# LPCB226_-_TOP_OVERVIEW.net
KiCad netlist of a schematic drawn in Altium Designer
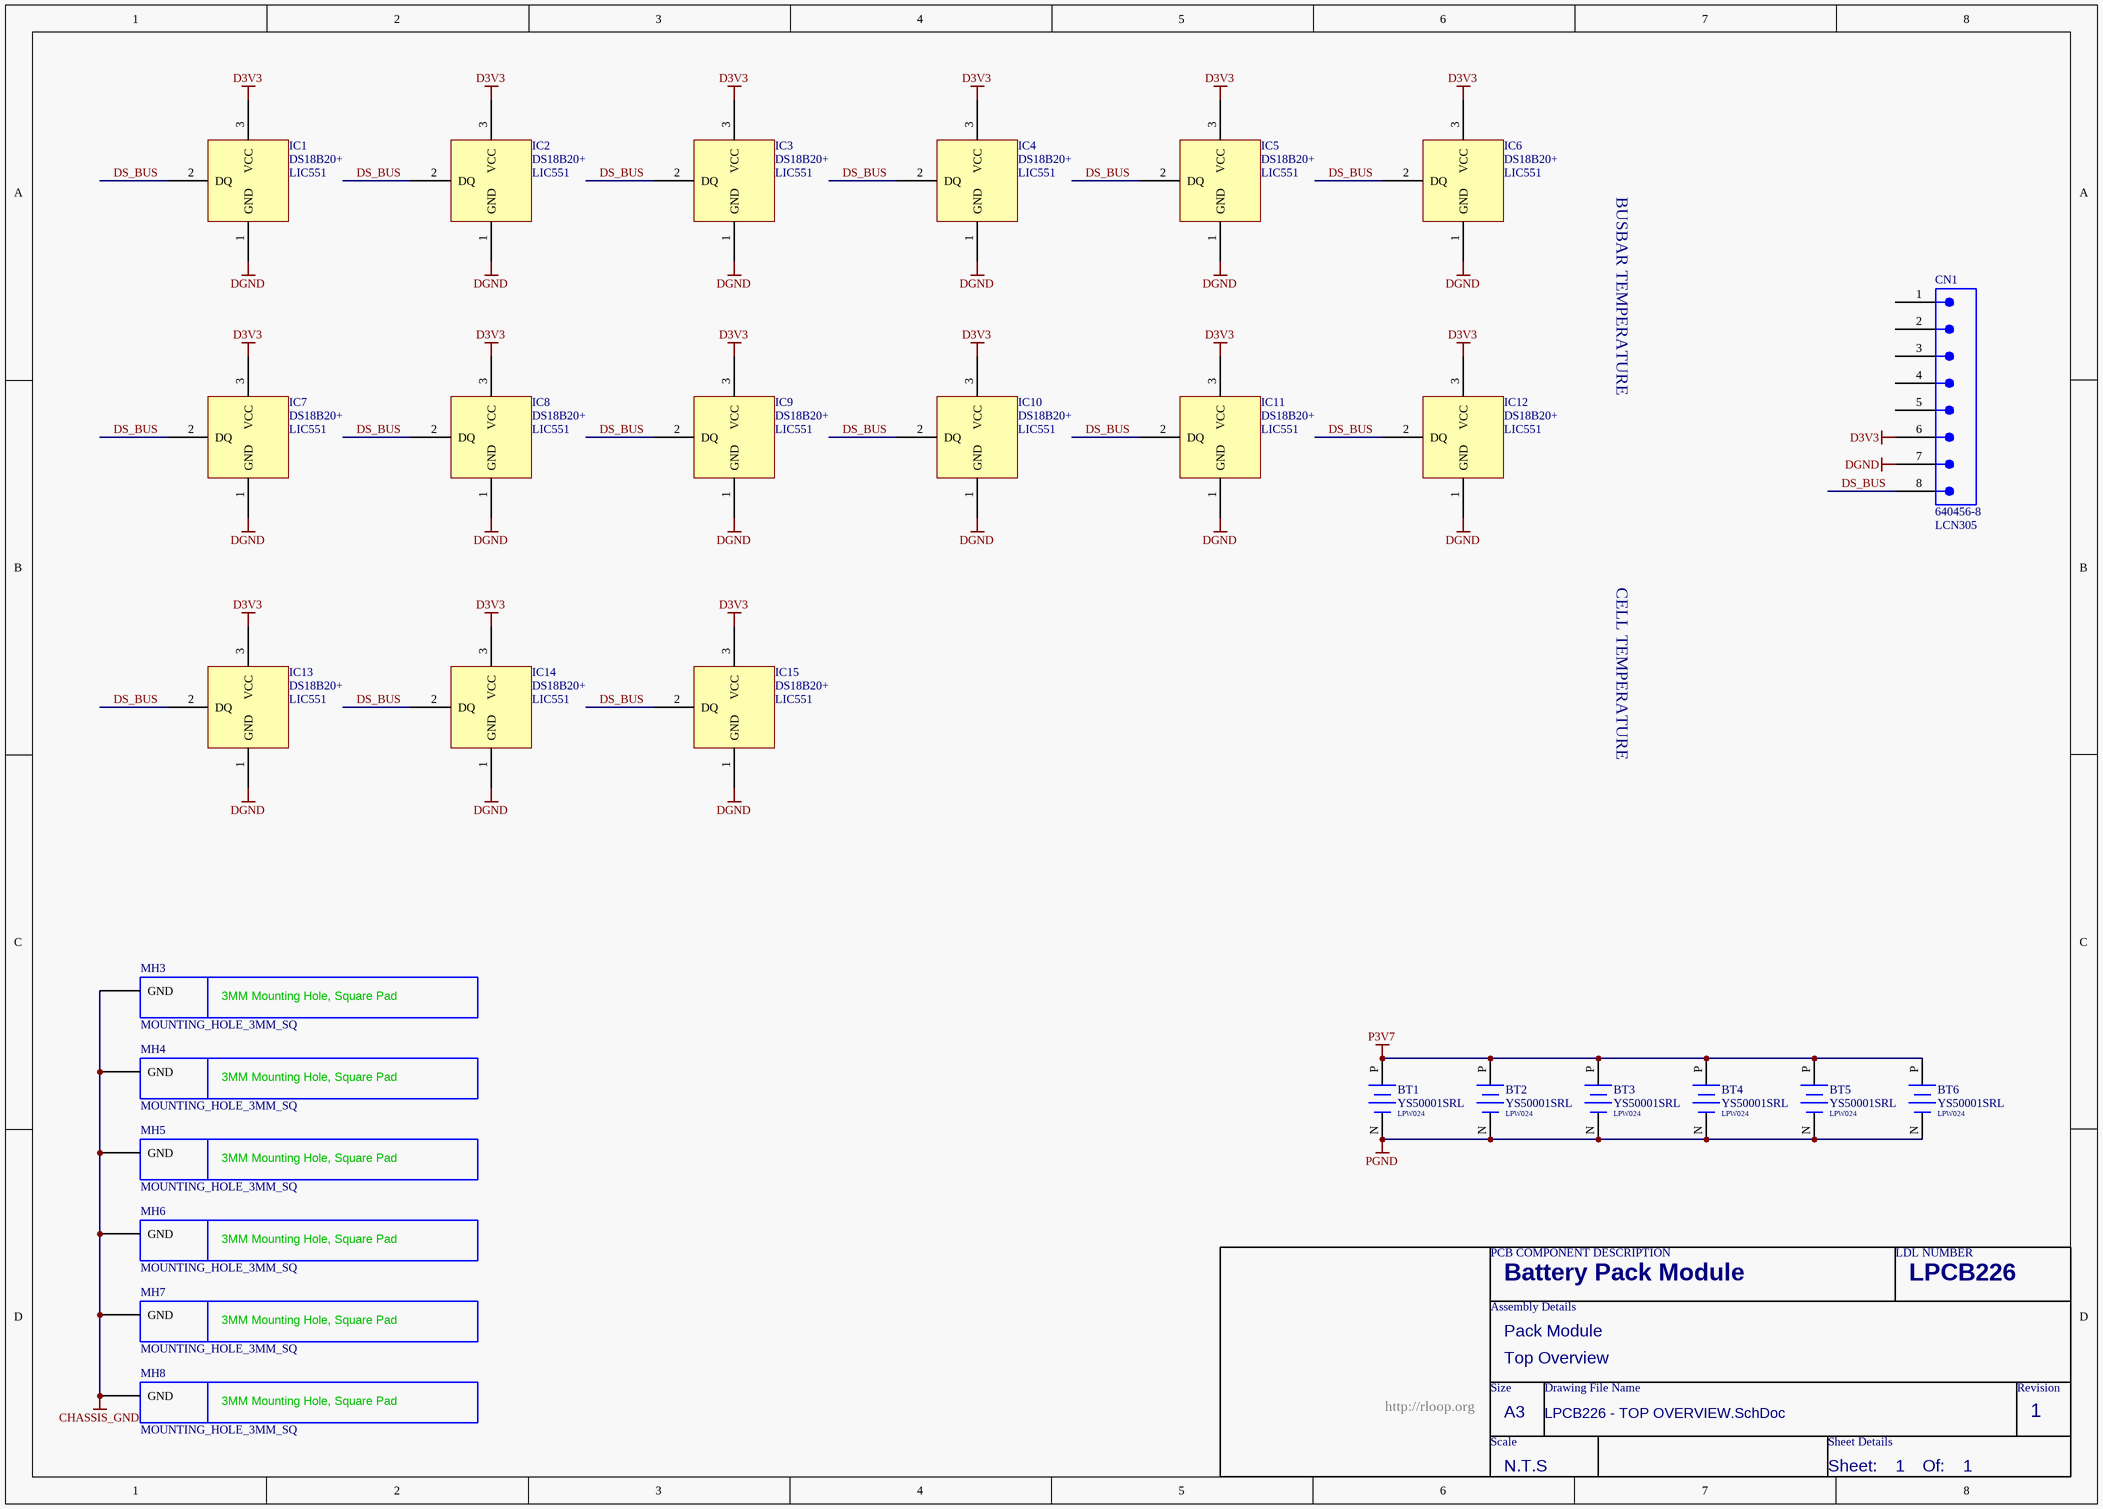
[diagram p0: LPCB226 - TOP OVERVIEW.SchDoc]

(export (version "E")
  (design (tool "Eeschema 10.0.6"))
  (components
    (comp (ref "BT1")
      (value "YS50001SRL")
      (footprint "YS50001SRL")
      (description "Battery, LiPo")
      (fields (field (name "LDL_NUMBER") "LPW024"))
      (libsource (lib "LDL_Power") (part "YS50001SRL"))
    )
    (comp (ref "BT2")
      (value "YS50001SRL")
      (footprint "YS50001SRL")
      (description "Battery, LiPo")
      (fields (field (name "LDL_NUMBER") "LPW024"))
      (libsource (lib "LDL_Power") (part "YS50001SRL"))
    )
    (comp (ref "BT3")
      (value "YS50001SRL")
      (footprint "YS50001SRL")
      (description "Battery, LiPo")
      (fields (field (name "LDL_NUMBER") "LPW024"))
      (libsource (lib "LDL_Power") (part "YS50001SRL"))
    )
    (comp (ref "BT4")
      (value "YS50001SRL")
      (footprint "YS50001SRL")
      (description "Battery, LiPo")
      (fields (field (name "LDL_NUMBER") "LPW024"))
      (libsource (lib "LDL_Power") (part "YS50001SRL"))
    )
    (comp (ref "BT5")
      (value "YS50001SRL")
      (footprint "YS50001SRL")
      (description "Battery, LiPo")
      (fields (field (name "LDL_NUMBER") "LPW024"))
      (libsource (lib "LDL_Power") (part "YS50001SRL"))
    )
    (comp (ref "BT6")
      (value "YS50001SRL")
      (footprint "YS50001SRL")
      (description "Battery, LiPo")
      (fields (field (name "LDL_NUMBER") "LPW024"))
      (libsource (lib "LDL_Power") (part "YS50001SRL"))
    )
    (comp (ref "CN1")
      (value "640456-8")
      (footprint "640456-8")
      (description "Connector, Male Header, 8 Way")
      (fields (field (name "LDL_NUMBER") "LCN305"))
      (libsource (lib "LDL_Connectors") (part "640456-8"))
    )
    (comp (ref "IC1")
      (value "DS18B20+")
      (footprint "TO-92A")
      (description "IC, Temperature Sensor, 1 Wire, PTH")
      (fields (field (name "LDL_NUMBER") "LIC551"))
      (libsource (lib "LDL_Semiconductors") (part "DS18B20+"))
    )
    (comp (ref "IC2")
      (value "DS18B20+")
      (footprint "TO-92A")
      (description "IC, Temperature Sensor, 1 Wire, PTH")
      (fields (field (name "LDL_NUMBER") "LIC551"))
      (libsource (lib "LDL_Semiconductors") (part "DS18B20+"))
    )
    (comp (ref "IC3")
      (value "DS18B20+")
      (footprint "TO-92A")
      (description "IC, Temperature Sensor, 1 Wire, PTH")
      (fields (field (name "LDL_NUMBER") "LIC551"))
      (libsource (lib "LDL_Semiconductors") (part "DS18B20+"))
    )
    (comp (ref "IC4")
      (value "DS18B20+")
      (footprint "TO-92A")
      (description "IC, Temperature Sensor, 1 Wire, PTH")
      (fields (field (name "LDL_NUMBER") "LIC551"))
      (libsource (lib "LDL_Semiconductors") (part "DS18B20+"))
    )
    (comp (ref "IC5")
      (value "DS18B20+")
      (footprint "TO-92A")
      (description "IC, Temperature Sensor, 1 Wire, PTH")
      (fields (field (name "LDL_NUMBER") "LIC551"))
      (libsource (lib "LDL_Semiconductors") (part "DS18B20+"))
    )
    (comp (ref "IC6")
      (value "DS18B20+")
      (footprint "TO-92A")
      (description "IC, Temperature Sensor, 1 Wire, PTH")
      (fields (field (name "LDL_NUMBER") "LIC551"))
      (libsource (lib "LDL_Semiconductors") (part "DS18B20+"))
    )
    (comp (ref "IC7")
      (value "DS18B20+")
      (footprint "TO-92A")
      (description "IC, Temperature Sensor, 1 Wire, PTH")
      (fields (field (name "LDL_NUMBER") "LIC551"))
      (libsource (lib "LDL_Semiconductors") (part "DS18B20+"))
    )
    (comp (ref "IC8")
      (value "DS18B20+")
      (footprint "TO-92A")
      (description "IC, Temperature Sensor, 1 Wire, PTH")
      (fields (field (name "LDL_NUMBER") "LIC551"))
      (libsource (lib "LDL_Semiconductors") (part "DS18B20+"))
    )
    (comp (ref "IC9")
      (value "DS18B20+")
      (footprint "TO-92A")
      (description "IC, Temperature Sensor, 1 Wire, PTH")
      (fields (field (name "LDL_NUMBER") "LIC551"))
      (libsource (lib "LDL_Semiconductors") (part "DS18B20+"))
    )
    (comp (ref "IC10")
      (value "DS18B20+")
      (footprint "TO-92A")
      (description "IC, Temperature Sensor, 1 Wire, PTH")
      (fields (field (name "LDL_NUMBER") "LIC551"))
      (libsource (lib "LDL_Semiconductors") (part "DS18B20+"))
    )
    (comp (ref "IC11")
      (value "DS18B20+")
      (footprint "TO-92A")
      (description "IC, Temperature Sensor, 1 Wire, PTH")
      (fields (field (name "LDL_NUMBER") "LIC551"))
      (libsource (lib "LDL_Semiconductors") (part "DS18B20+"))
    )
    (comp (ref "IC12")
      (value "DS18B20+")
      (footprint "TO-92A")
      (description "IC, Temperature Sensor, 1 Wire, PTH")
      (fields (field (name "LDL_NUMBER") "LIC551"))
      (libsource (lib "LDL_Semiconductors") (part "DS18B20+"))
    )
    (comp (ref "IC13")
      (value "DS18B20+")
      (footprint "TO-92A")
      (description "IC, Temperature Sensor, 1 Wire, PTH")
      (fields (field (name "LDL_NUMBER") "LIC551"))
      (libsource (lib "LDL_Semiconductors") (part "DS18B20+"))
    )
    (comp (ref "IC14")
      (value "DS18B20+")
      (footprint "TO-92A")
      (description "IC, Temperature Sensor, 1 Wire, PTH")
      (fields (field (name "LDL_NUMBER") "LIC551"))
      (libsource (lib "LDL_Semiconductors") (part "DS18B20+"))
    )
    (comp (ref "IC15")
      (value "DS18B20+")
      (footprint "TO-92A")
      (description "IC, Temperature Sensor, 1 Wire, PTH")
      (fields (field (name "LDL_NUMBER") "LIC551"))
      (libsource (lib "LDL_Semiconductors") (part "DS18B20+"))
    )
    (comp (ref "MH3")
      (value "MOUNTING_HOLE_3MM_SQ")
      (footprint "MOUNTING_HOLE_3MM_SQ")
      (description "3MM Mouting Hole, Square")
      (libsource (lib "LDL_Mechanical") (part "MOUNTING_HOLE_3MM_SQ"))
    )
    (comp (ref "MH4")
      (value "MOUNTING_HOLE_3MM_SQ")
      (footprint "MOUNTING_HOLE_3MM_SQ")
      (description "3MM Mouting Hole, Square")
      (libsource (lib "LDL_Mechanical") (part "MOUNTING_HOLE_3MM_SQ"))
    )
    (comp (ref "MH5")
      (value "MOUNTING_HOLE_3MM_SQ")
      (footprint "MOUNTING_HOLE_3MM_SQ")
      (description "3MM Mouting Hole, Square")
      (libsource (lib "LDL_Mechanical") (part "MOUNTING_HOLE_3MM_SQ"))
    )
    (comp (ref "MH6")
      (value "MOUNTING_HOLE_3MM_SQ")
      (footprint "MOUNTING_HOLE_3MM_SQ")
      (description "3MM Mouting Hole, Square")
      (libsource (lib "LDL_Mechanical") (part "MOUNTING_HOLE_3MM_SQ"))
    )
    (comp (ref "MH7")
      (value "MOUNTING_HOLE_3MM_SQ")
      (footprint "MOUNTING_HOLE_3MM_SQ")
      (description "3MM Mouting Hole, Square")
      (libsource (lib "LDL_Mechanical") (part "MOUNTING_HOLE_3MM_SQ"))
    )
    (comp (ref "MH8")
      (value "MOUNTING_HOLE_3MM_SQ")
      (footprint "MOUNTING_HOLE_3MM_SQ")
      (description "3MM Mouting Hole, Square")
      (libsource (lib "LDL_Mechanical") (part "MOUNTING_HOLE_3MM_SQ"))
    )
  )
  (nets
    (net (code "1") (name "/DS_BUS") (class "Default")
      (node (ref "CN1") (pin "8") (pinfunction "8_8") (pintype "passive"))
      (node (ref "IC1") (pin "2") (pinfunction "DQ_2") (pintype "passive"))
      (node (ref "IC10") (pin "2") (pinfunction "DQ_2") (pintype "passive"))
      (node (ref "IC11") (pin "2") (pinfunction "DQ_2") (pintype "passive"))
      (node (ref "IC12") (pin "2") (pinfunction "DQ_2") (pintype "passive"))
      (node (ref "IC13") (pin "2") (pinfunction "DQ_2") (pintype "passive"))
      (node (ref "IC14") (pin "2") (pinfunction "DQ_2") (pintype "passive"))
      (node (ref "IC15") (pin "2") (pinfunction "DQ_2") (pintype "passive"))
      (node (ref "IC2") (pin "2") (pinfunction "DQ_2") (pintype "passive"))
      (node (ref "IC3") (pin "2") (pinfunction "DQ_2") (pintype "passive"))
      (node (ref "IC4") (pin "2") (pinfunction "DQ_2") (pintype "passive"))
      (node (ref "IC5") (pin "2") (pinfunction "DQ_2") (pintype "passive"))
      (node (ref "IC6") (pin "2") (pinfunction "DQ_2") (pintype "passive"))
      (node (ref "IC7") (pin "2") (pinfunction "DQ_2") (pintype "passive"))
      (node (ref "IC8") (pin "2") (pinfunction "DQ_2") (pintype "passive"))
      (node (ref "IC9") (pin "2") (pinfunction "DQ_2") (pintype "passive"))
    )
    (net (code "2") (name "CHASSIS_GND") (class "Default")
      (node (ref "MH3") (pin "MOUNT") (pinfunction "GND_MOUNT") (pintype "passive"))
      (node (ref "MH4") (pin "MOUNT") (pinfunction "GND_MOUNT") (pintype "passive"))
      (node (ref "MH5") (pin "MOUNT") (pinfunction "GND_MOUNT") (pintype "passive"))
      (node (ref "MH6") (pin "MOUNT") (pinfunction "GND_MOUNT") (pintype "passive"))
      (node (ref "MH7") (pin "MOUNT") (pinfunction "GND_MOUNT") (pintype "passive"))
      (node (ref "MH8") (pin "MOUNT") (pinfunction "GND_MOUNT") (pintype "passive"))
    )
    (net (code "3") (name "D3V3") (class "Default")
      (node (ref "CN1") (pin "6") (pinfunction "6_6") (pintype "passive"))
      (node (ref "IC1") (pin "3") (pinfunction "VCC_3") (pintype "power_in"))
      (node (ref "IC10") (pin "3") (pinfunction "VCC_3") (pintype "power_in"))
      (node (ref "IC11") (pin "3") (pinfunction "VCC_3") (pintype "power_in"))
      (node (ref "IC12") (pin "3") (pinfunction "VCC_3") (pintype "power_in"))
      (node (ref "IC13") (pin "3") (pinfunction "VCC_3") (pintype "power_in"))
      (node (ref "IC14") (pin "3") (pinfunction "VCC_3") (pintype "power_in"))
      (node (ref "IC15") (pin "3") (pinfunction "VCC_3") (pintype "power_in"))
      (node (ref "IC2") (pin "3") (pinfunction "VCC_3") (pintype "power_in"))
      (node (ref "IC3") (pin "3") (pinfunction "VCC_3") (pintype "power_in"))
      (node (ref "IC4") (pin "3") (pinfunction "VCC_3") (pintype "power_in"))
      (node (ref "IC5") (pin "3") (pinfunction "VCC_3") (pintype "power_in"))
      (node (ref "IC6") (pin "3") (pinfunction "VCC_3") (pintype "power_in"))
      (node (ref "IC7") (pin "3") (pinfunction "VCC_3") (pintype "power_in"))
      (node (ref "IC8") (pin "3") (pinfunction "VCC_3") (pintype "power_in"))
      (node (ref "IC9") (pin "3") (pinfunction "VCC_3") (pintype "power_in"))
    )
    (net (code "4") (name "DGND") (class "Default")
      (node (ref "CN1") (pin "7") (pinfunction "7_7") (pintype "passive"))
      (node (ref "IC1") (pin "1") (pinfunction "GND_1") (pintype "power_in"))
      (node (ref "IC10") (pin "1") (pinfunction "GND_1") (pintype "power_in"))
      (node (ref "IC11") (pin "1") (pinfunction "GND_1") (pintype "power_in"))
      (node (ref "IC12") (pin "1") (pinfunction "GND_1") (pintype "power_in"))
      (node (ref "IC13") (pin "1") (pinfunction "GND_1") (pintype "power_in"))
      (node (ref "IC14") (pin "1") (pinfunction "GND_1") (pintype "power_in"))
      (node (ref "IC15") (pin "1") (pinfunction "GND_1") (pintype "power_in"))
      (node (ref "IC2") (pin "1") (pinfunction "GND_1") (pintype "power_in"))
      (node (ref "IC3") (pin "1") (pinfunction "GND_1") (pintype "power_in"))
      (node (ref "IC4") (pin "1") (pinfunction "GND_1") (pintype "power_in"))
      (node (ref "IC5") (pin "1") (pinfunction "GND_1") (pintype "power_in"))
      (node (ref "IC6") (pin "1") (pinfunction "GND_1") (pintype "power_in"))
      (node (ref "IC7") (pin "1") (pinfunction "GND_1") (pintype "power_in"))
      (node (ref "IC8") (pin "1") (pinfunction "GND_1") (pintype "power_in"))
      (node (ref "IC9") (pin "1") (pinfunction "GND_1") (pintype "power_in"))
    )
    (net (code "5") (name "P3V7") (class "Default")
      (node (ref "BT1") (pin "P") (pinfunction "+_P") (pintype "passive"))
      (node (ref "BT2") (pin "P") (pinfunction "+_P") (pintype "passive"))
      (node (ref "BT3") (pin "P") (pinfunction "+_P") (pintype "passive"))
      (node (ref "BT4") (pin "P") (pinfunction "+_P") (pintype "passive"))
      (node (ref "BT5") (pin "P") (pinfunction "+_P") (pintype "passive"))
      (node (ref "BT6") (pin "P") (pinfunction "+_P") (pintype "passive"))
    )
    (net (code "6") (name "PGND") (class "Default")
      (node (ref "BT1") (pin "N") (pinfunction "-_N") (pintype "passive"))
      (node (ref "BT2") (pin "N") (pinfunction "-_N") (pintype "passive"))
      (node (ref "BT3") (pin "N") (pinfunction "-_N") (pintype "passive"))
      (node (ref "BT4") (pin "N") (pinfunction "-_N") (pintype "passive"))
      (node (ref "BT5") (pin "N") (pinfunction "-_N") (pintype "passive"))
      (node (ref "BT6") (pin "N") (pinfunction "-_N") (pintype "passive"))
    )
    (net (code "7") (name "unconnected-(CN1-Pad1)") (class "Default")
      (node (ref "CN1") (pin "1") (pinfunction "1_1") (pintype "passive"))
    )
    (net (code "8") (name "unconnected-(CN1-Pad2)") (class "Default")
      (node (ref "CN1") (pin "2") (pinfunction "2_2") (pintype "passive"))
    )
    (net (code "9") (name "unconnected-(CN1-Pad3)") (class "Default")
      (node (ref "CN1") (pin "3") (pinfunction "3_3") (pintype "passive"))
    )
    (net (code "10") (name "unconnected-(CN1-Pad4)") (class "Default")
      (node (ref "CN1") (pin "4") (pinfunction "4_4") (pintype "passive"))
    )
    (net (code "11") (name "unconnected-(CN1-Pad5)") (class "Default")
      (node (ref "CN1") (pin "5") (pinfunction "5_5") (pintype "passive"))
    )
  )
)
